# SHT_4_MCU_07349-R5_L10.net
KiCad netlist of a schematic drawn in Altium Designer
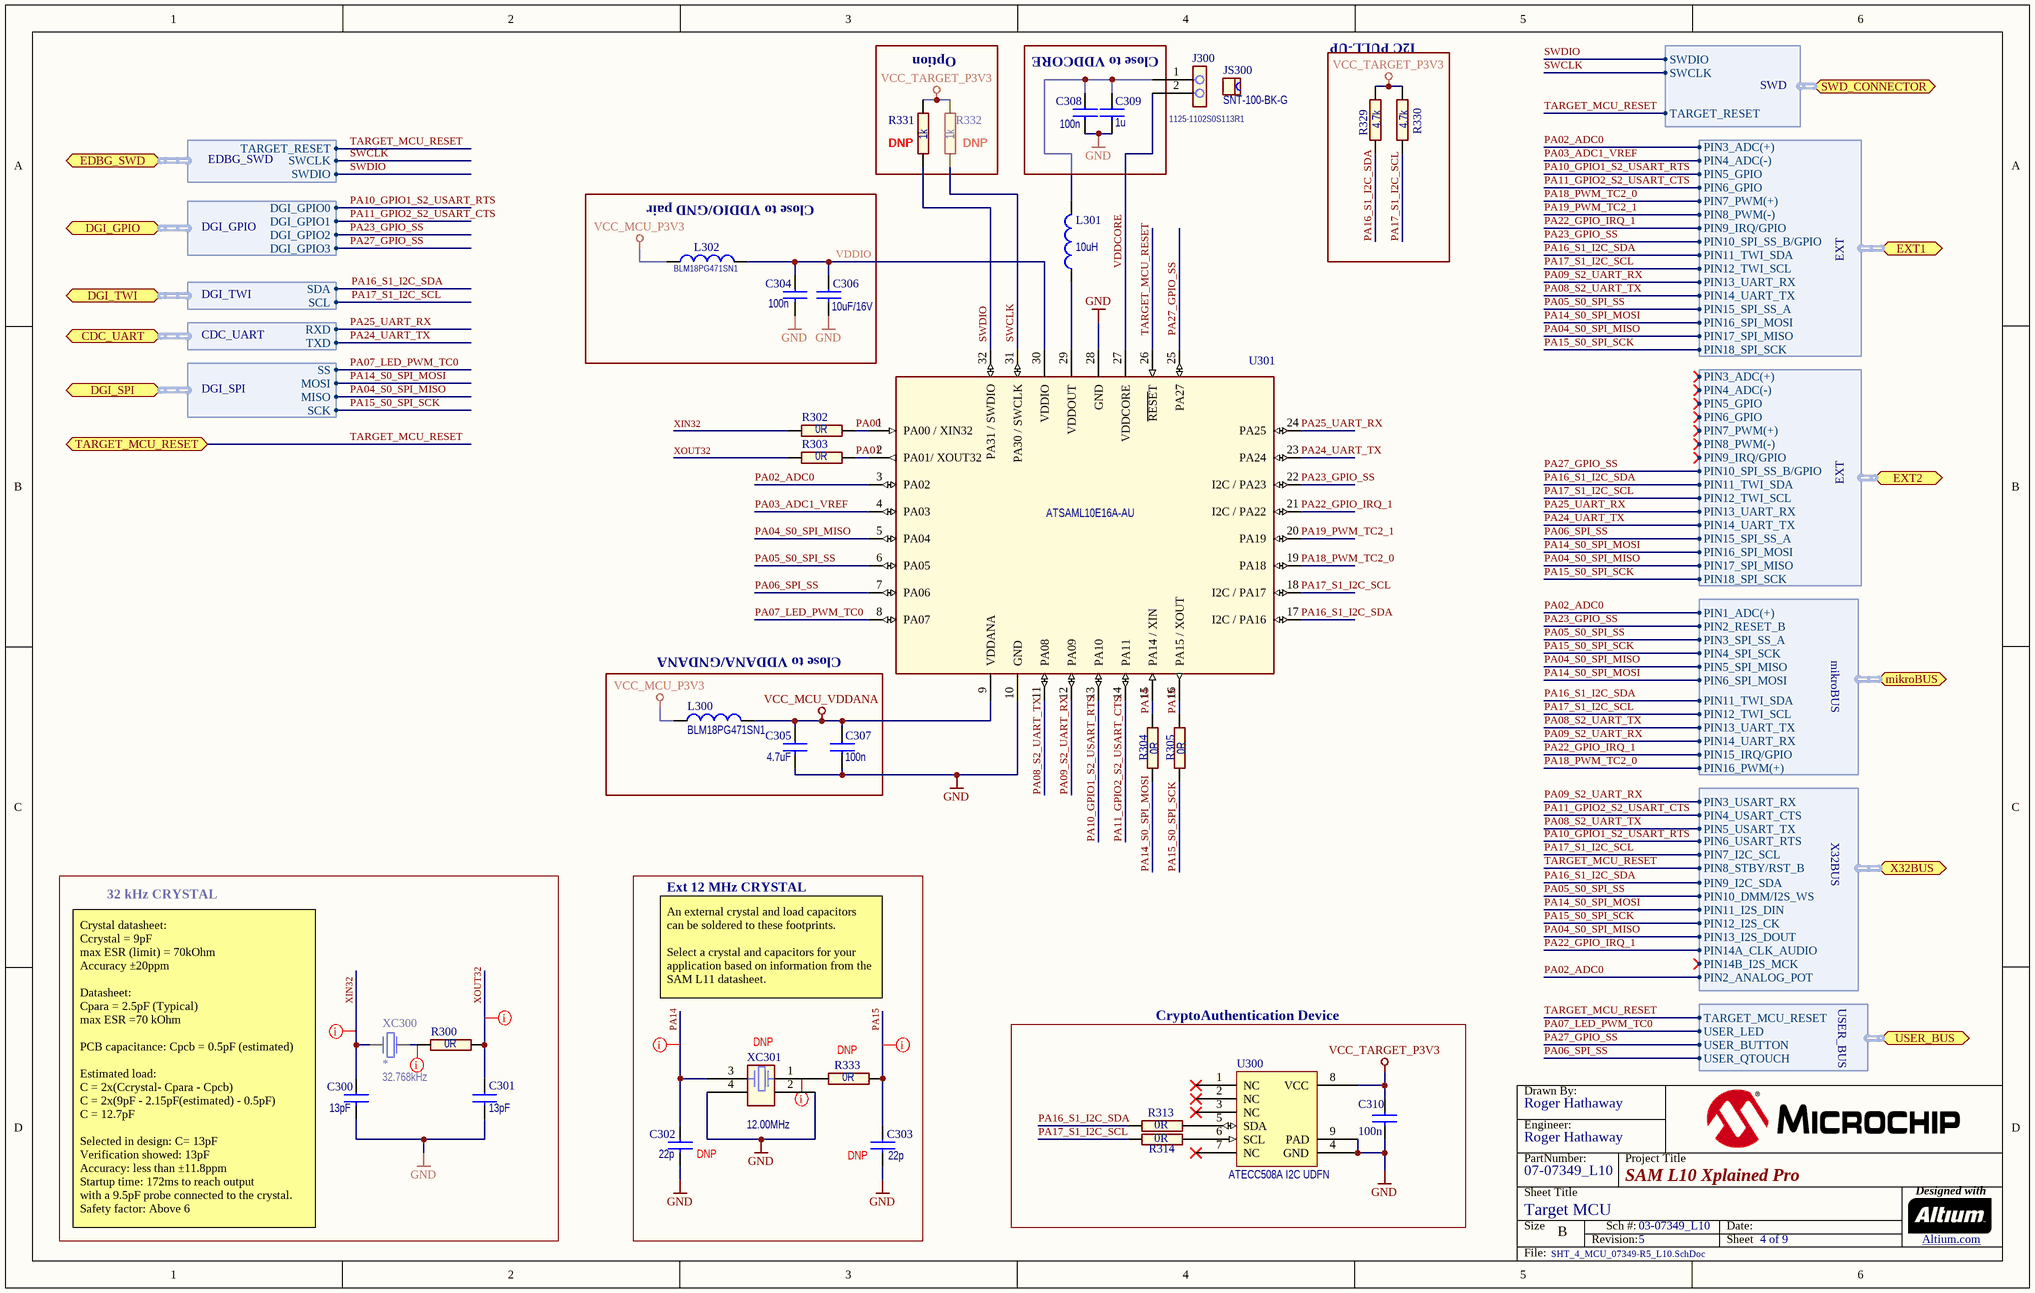
[diagram p0: SHT_4_MCU_07349-R5_L10.SchDoc]

(export (version "E")
  (design (tool "Eeschema 10.0.6"))
  (components
    (comp (ref "C300")
      (value "13pF")
      (footprint "AP1-00053")
      (description "Ceramic capacitor, SMD 0402, NP0, 50V, +/-5%")
      (fields
        (field (name "TOLERANCE") "5%")
        (field (name "MANUFACTURER") "Murata")
        (field (name "VERIFIED BY") "Lars Helge Mo")
      )
      (libsource (lib "AltiumDbLib") (part "CAP-NONPOL"))
    )
    (comp (ref "C301")
      (value "13pF")
      (footprint "AP1-00053")
      (description "Ceramic capacitor, SMD 0402, NP0, 50V, +/-5%")
      (fields
        (field (name "TOLERANCE") "5%")
        (field (name "MANUFACTURER") "Murata")
        (field (name "VERIFIED BY") "Lars Helge Mo")
      )
      (libsource (lib "AltiumDbLib") (part "CAP-NONPOL"))
    )
    (comp (ref "C302")
      (value "22p")
      (footprint "AP1-00001")
      (description "Ceramic capacitor, SMD 0402, NP0, 50V, +/-5%")
      (fields
        (field (name "TOLERANCE") "50V, +/-5%")
        (field (name "MANUFACTURER") "YAGEO CORP")
        (field (name "PLACEMENT") "DNP")
        (field (name "VERIFIED BY") "Lars Helge Mo")
      )
      (libsource (lib "AltiumDbLib") (part "CAP-NONPOL"))
    )
    (comp (ref "C303")
      (value "22p")
      (footprint "AP1-00001")
      (description "Ceramic capacitor, SMD 0402, NP0, 50V, +/-5%")
      (fields
        (field (name "TOLERANCE") "50V, +/-5%")
        (field (name "MANUFACTURER") "YAGEO CORP")
        (field (name "PLACEMENT") "DNP")
        (field (name "VERIFIED BY") "Lars Helge Mo")
      )
      (libsource (lib "AltiumDbLib") (part "CAP-NONPOL"))
    )
    (comp (ref "C304")
      (value "100n")
      (footprint "AP1-00001")
      (description "Ceramic capacitor, SMD 0402, X7R, 16V, +/-10%")
      (fields
        (field (name "TOLERANCE") "16V, +/-10%")
        (field (name "MANUFACTURER") "Kemet")
        (field (name "VERIFIED BY") "Lars Helge Mo")
      )
      (libsource (lib "AltiumDbLib") (part "CAP-NONPOL"))
    )
    (comp (ref "C305")
      (value "4.7uF")
      (footprint "AP1-00039")
      (description "Ceramic capacitor, SMD 0603, X5R, 10V, 10% (de31036)")
      (fields
        (field (name "TOLERANCE") "10%")
        (field (name "MANUFACTURER") "WALSIN Technology Corporation")
        (field (name "VERIFIED BY") "Lars Helge Mo")
      )
      (libsource (lib "AltiumDbLib") (part "CAP-NONPOL"))
    )
    (comp (ref "C306")
      (value "10uF/16V")
      (footprint "AP1-00039")
      (description "Ceramic capacitor, SMD 0603, X5R, 16V, 10UF ± 20% (High Density)")
      (fields
        (field (name "TOLERANCE") "­± 20%")
        (field (name "MANUFACTURER") "Taiyo Yuden")
        (field (name "VERIFIED BY") "Lars Helge Mo")
      )
      (libsource (lib "AltiumDbLib") (part "CAP-NONPOL"))
    )
    (comp (ref "C307")
      (value "100n")
      (footprint "AP1-00001")
      (description "Ceramic capacitor, SMD 0402, X7R, 16V, +/-10%")
      (fields
        (field (name "TOLERANCE") "16V, +/-10%")
        (field (name "MANUFACTURER") "Kemet")
        (field (name "VERIFIED BY") "Lars Helge Mo")
      )
      (libsource (lib "AltiumDbLib") (part "CAP-NONPOL"))
    )
    (comp (ref "C308")
      (value "100n")
      (footprint "AP1-00001")
      (description "Ceramic capacitor, SMD 0402, X7R, 16V, +/-10%")
      (fields
        (field (name "TOLERANCE") "16V, +/-10%")
        (field (name "MANUFACTURER") "Kemet")
        (field (name "VERIFIED BY") "Lars Helge Mo")
      )
      (libsource (lib "AltiumDbLib") (part "CAP-NONPOL"))
    )
    (comp (ref "C309")
      (value "1u")
      (footprint "AP1-00001")
      (description "Ceramic capacitor, SMD 0402, X5R, 6.3V, +/-10% (de26942)")
      (fields
        (field (name "TOLERANCE") "+/-10%")
        (field (name "MANUFACTURER") "Kemet")
        (field (name "VERIFIED BY") "Lars Helge Mo")
      )
      (libsource (lib "AltiumDbLib") (part "CAP-NONPOL"))
    )
    (comp (ref "C310")
      (value "100n")
      (footprint "AltiumDbLib:AP1-00053")
      (description "Ceramic capacitor, SMD 0402, X7R, 16V, +/-10%")
      (fields
        (field (name "TOLERANCE") "16V, +/-10%")
        (field (name "MANUFACTURER") "Kemet")
        (field (name "VERIFIED BY") "Lars Helge Mo")
      )
      (libsource (lib "AltiumDbLib") (part "CAP-NONPOL"))
    )
    (comp (ref "J300")
      (value "HEADER 1x2")
      (footprint "AP8-01074")
      (description "1x2 pin header, 2.54mm pitch, Pin-in-Paste THM")
      (fields
        (field (name "MANUFACTURER") "WCON HARDWARE ELECTRONICS CO., LTD")
        (field (name "MPN") "1125-1102S0S113R1")
        (field (name "VERIFIED BY") "Lars Helge")
      )
      (libsource (lib "AltiumDbLib") (part "HEADER 1x2"))
    )
    (comp (ref "JS300")
      (value "SNT-100-BK-G")
      (footprint "AP8-00525")
      (description "Jumper cap for 2.54mm pinheader")
      (fields
        (field (name "MANUFACTURER") "SAMTEC")
        (field (name "Comment") "To be used by request from ESCATEC")
        (field (name "VERIFIED BY") "Lars Helge Mo")
      )
      (libsource (lib "AltiumDbLib") (part "JUMPER_CAP"))
    )
    (comp (ref "L300")
      (value "BLM18PG471SN1")
      (footprint "AP3-00005")
      (description "SMD RF inductor 0603. Z=470Ohm (@100MHz), Max R(dc)=0.20Ohm, Max current=1A")
      (fields
        (field (name "MANUFACTURER") "Murata")
        (field (name "Comment") "INDUCTOR")
        (field (name "VERIFIED BY") "Lars Helge Mo")
      )
      (libsource (lib "") (part "INDUCTOR_1"))
    )
    (comp (ref "L301")
      (value "10uH")
      (footprint "AP3-00157")
      (description "SMD power inductor, LxWxH=3.0x3.0x2.0mm, Isat=2.35A, Ir=1.2A, Rdc=0.28Ohm, 20%")
      (fields
        (field (name "TOLERANCE") "20%")
        (field (name "MANUFACTURER") "Wurth Elektronik")
        (field (name "VERIFIED BY") "Lars Helge Mo")
      )
      (libsource (lib "AltiumDbLib") (part "INDUCTOR"))
    )
    (comp (ref "L302")
      (value "BLM18PG471SN1")
      (footprint "AP3-00005")
      (description "SMD RF inductor 0603. Z=470Ohm (@100MHz), Max R(dc)=0.20Ohm, Max current=1A")
      (fields
        (field (name "MANUFACTURER") "Murata")
        (field (name "Comment") "INDUCTOR")
        (field (name "VERIFIED BY") "Lars Helge Mo")
      )
      (libsource (lib "AltiumDbLib") (part "INDUCTOR"))
    )
    (comp (ref "R300")
      (value "0R")
      (footprint "AP2-00000")
      (description "RES 0.0 OHM 1/16W 0402 SMD")
      (fields
        (field (name "TOLERANCE") "1 %")
        (field (name "MANUFACTURER") "(n/a)")
        (field (name "VERIFIED BY") "Lars Helge Mo")
      )
      (libsource (lib "") (part "R2_2"))
    )
    (comp (ref "R302")
      (value "0R")
      (footprint "AP2-00000")
      (description "RES 0.0 OHM 1/16W 0402 SMD")
      (fields
        (field (name "TOLERANCE") "1 %")
        (field (name "MANUFACTURER") "(n/a)")
        (field (name "VERIFIED BY") "Lars Helge Mo")
      )
      (libsource (lib "") (part "R2_2"))
    )
    (comp (ref "R303")
      (value "0R")
      (footprint "AP2-00000")
      (description "RES 0.0 OHM 1/16W 0402 SMD")
      (fields
        (field (name "TOLERANCE") "1 %")
        (field (name "MANUFACTURER") "(n/a)")
        (field (name "VERIFIED BY") "Lars Helge Mo")
      )
      (libsource (lib "") (part "R2_2"))
    )
    (comp (ref "R304")
      (value "0R")
      (footprint "AP2-00000")
      (description "RES 0.0 OHM 1/16W 0402 SMD")
      (fields
        (field (name "TOLERANCE") "1 %")
        (field (name "MANUFACTURER") "(n/a)")
        (field (name "VERIFIED BY") "Lars Helge Mo")
      )
      (libsource (lib "") (part "R2_1"))
    )
    (comp (ref "R305")
      (value "0R")
      (footprint "AP2-00000")
      (description "RES 0.0 OHM 1/16W 0402 SMD")
      (fields
        (field (name "TOLERANCE") "1 %")
        (field (name "MANUFACTURER") "(n/a)")
        (field (name "VERIFIED BY") "Lars Helge Mo")
      )
      (libsource (lib "") (part "R2_1"))
    )
    (comp (ref "R313")
      (value "0R")
      (footprint "AP2-00000")
      (description "RES 0.0 OHM 1/16W 0402 SMD")
      (fields
        (field (name "TOLERANCE") "1 %")
        (field (name "MANUFACTURER") "(n/a)")
        (field (name "VERIFIED BY") "Lars Helge Mo")
      )
      (libsource (lib "") (part "R2_3"))
    )
    (comp (ref "R314")
      (value "0R")
      (footprint "AP2-00000")
      (description "RES 0.0 OHM 1/16W 0402 SMD")
      (fields
        (field (name "TOLERANCE") "1 %")
        (field (name "MANUFACTURER") "(n/a)")
        (field (name "VERIFIED BY") "Lars Helge Mo")
      )
      (libsource (lib "") (part "R2_3"))
    )
    (comp (ref "R329")
      (value "4.7k")
      (footprint "AP2-00032")
      (description "Thick film resistor, SMD 0402, 1/16W, 5%")
      (fields
        (field (name "TOLERANCE") "5%")
        (field (name "MANUFACTURER") "(n/a)")
        (field (name "VERIFIED BY") "Lars Helge Mo")
      )
      (libsource (lib "AltiumDbLib") (part "R2"))
    )
    (comp (ref "R330")
      (value "4.7k")
      (footprint "AP2-00032")
      (description "Thick film resistor, SMD 0402, 1/16W, 5%")
      (fields
        (field (name "TOLERANCE") "5%")
        (field (name "MANUFACTURER") "(n/a)")
        (field (name "VERIFIED BY") "Lars Helge Mo")
      )
      (libsource (lib "AltiumDbLib") (part "R2"))
    )
    (comp (ref "R331")
      (value "1k")
      (footprint "AP2-00000")
      (description "Thick film resistor, SMD 0402, 1/16W, 1%")
      (fields
        (field (name "TOLERANCE") "1 %")
        (field (name "MANUFACTURER") "ASJ")
        (field (name "PLACEMENT") "DNP")
        (field (name "VERIFIED BY") "Lars Helge Mo")
      )
      (libsource (lib "AltiumDbLib") (part "R2"))
    )
    (comp (ref "R332")
      (value "1k")
      (footprint "AP2-00000")
      (description "Thick film resistor, SMD 0402, 1/16W, 1%")
      (fields
        (field (name "TOLERANCE") "1 %")
        (field (name "MANUFACTURER") "ASJ")
        (field (name "PLACEMENT") "DNP")
        (field (name "VERIFIED BY") "Lars Helge Mo")
      )
      (libsource (lib "AltiumDbLib") (part "R2"))
    )
    (comp (ref "R333")
      (value "0R")
      (footprint "AP2-00000")
      (description "RES 0.0 OHM 1/16W 0402 SMD")
      (fields
        (field (name "TOLERANCE") "1 %")
        (field (name "MANUFACTURER") "(n/a)")
        (field (name "PLACEMENT") "DNP")
        (field (name "VERIFIED BY") "Lars Helge Mo")
      )
      (libsource (lib "AltiumDbLib") (part "R2"))
    )
    (comp (ref "U300")
      (value "ATECC508A I2C UDFN")
      (footprint "AP6-00409")
      (description "ATECC508A with an I2C Interface and a 8 Pin UDFN Package with Paddle")
      (fields (field (name "MANUFACTURER") "MICROCHIP") (field (name "MPN") "ATECC508A-MAHDA-T"))
      (libsource (lib "AltiumDbLib") (part "ATECC508A_I2C_UDFN"))
    )
    (comp (ref "U301")
      (value "ATSAML10E16A-AU")
      (footprint "AP6-00508")
      (description "32 Bit Ultra Low Power MCU w/ 64K Flash")
      (fields (field (name "MANUFACTURER") "Microchip") (field (name "VERIFIED BY") "*"))
      (libsource (lib "AltiumDbLib") (part "ATSAML10E16A-AU"))
    )
    (comp (ref "XC300")
      (value "*")
      (footprint "AP7-00090")
      (description "Kyocera ST3215SB32768E0HPWBB, 32.768kHz, 9pF, SMD tuning fork crystal")
      (fields
        (field (name "ALTIUM_VALUE") "32.768kHz")
        (field (name "TOLERANCE") "Â±20ppm")
        (field (name "MANUFACTURER") "Kyocera Crystal Device Corporation")
        (field (name "VERIFIED BY") "Sveinung Helgeland")
      )
      (libsource (lib "AltiumDbLib") (part "CRYSTAL"))
    )
    (comp (ref "XC301")
      (value "12.00MHz")
      (footprint "AP7-00039")
      (description "Fox FQ5032B 12.0000MHz  20pF SMD crystal 738B-12")
      (fields
        (field (name "TOLERANCE") "Â±30ppm")
        (field (name "MANUFACTURER") "Fox  Electronics")
        (field (name "PLACEMENT") "DNP")
        (field (name "VERIFIED BY") "Ketil Skjerve")
      )
      (libsource (lib "AltiumDbLib") (part "CRYSTAL1324"))
    )
  )
  (nets
    (net (code "11") (name "/PA00") (class "Default")
      (node (ref "R302") (pin "2") (pinfunction "2_2") (pintype "passive"))
      (node (ref "U301") (pin "1") (pinfunction "PA00_/_XIN32_1") (pintype "input"))
    )
    (net (code "12") (name "/PA01") (class "Default")
      (node (ref "R303") (pin "2") (pinfunction "2_2") (pintype "passive"))
      (node (ref "U301") (pin "2") (pinfunction "PA01/_XOUT32_2") (pintype "output"))
    )
    (net (code "13") (name "/PA02_ADC0") (class "Default")
      (node (ref "U301") (pin "3") (pinfunction "PA02_3") (pintype "bidirectional"))
    )
    (net (code "14") (name "/PA03_ADC1_VREF") (class "Default")
      (node (ref "U301") (pin "4") (pinfunction "PA03_4") (pintype "bidirectional"))
    )
    (net (code "15") (name "/PA04_S0_SPI_MISO") (class "Default")
      (node (ref "U301") (pin "5") (pinfunction "PA04_5") (pintype "bidirectional"))
    )
    (net (code "16") (name "/PA05_S0_SPI_SS") (class "Default")
      (node (ref "U301") (pin "6") (pinfunction "PA05_6") (pintype "bidirectional"))
    )
    (net (code "17") (name "/PA06_SPI_SS") (class "Default")
      (node (ref "U301") (pin "7") (pinfunction "PA06_7") (pintype "bidirectional"))
    )
    (net (code "18") (name "/PA07_LED_PWM_TC0") (class "Default")
      (node (ref "U301") (pin "8") (pinfunction "PA07_8") (pintype "bidirectional"))
    )
    (net (code "19") (name "/PA08_S2_UART_TX") (class "Default")
      (node (ref "U301") (pin "11") (pinfunction "PA08_11") (pintype "bidirectional"))
    )
    (net (code "20") (name "/PA09_S2_UART_RX") (class "Default")
      (node (ref "U301") (pin "12") (pinfunction "PA09_12") (pintype "bidirectional"))
    )
    (net (code "21") (name "/PA10_GPIO1_S2_USART_RTS") (class "Default")
      (node (ref "U301") (pin "13") (pinfunction "PA10_13") (pintype "bidirectional"))
    )
    (net (code "22") (name "/PA11_GPIO2_S2_USART_CTS") (class "Default")
      (node (ref "U301") (pin "14") (pinfunction "PA11_14") (pintype "bidirectional"))
    )
    (net (code "23") (name "/PA14") (class "Default")
      (node (ref "C302") (pin "1") (pinfunction "1_1") (pintype "passive"))
      (node (ref "R304") (pin "2") (pinfunction "2_2") (pintype "passive"))
      (node (ref "U301") (pin "15") (pinfunction "PA14_/_XIN_15") (pintype "input"))
      (node (ref "XC301") (pin "3") (pinfunction "3_3") (pintype "passive"))
    )
    (net (code "24") (name "/PA14_S0_SPI_MOSI") (class "Default")
      (node (ref "R304") (pin "1") (pinfunction "1_1") (pintype "passive"))
    )
    (net (code "25") (name "/PA15") (class "Default")
      (node (ref "C303") (pin "1") (pinfunction "1_1") (pintype "passive"))
      (node (ref "R305") (pin "2") (pinfunction "2_2") (pintype "passive"))
      (node (ref "R333") (pin "1") (pinfunction "1_1") (pintype "passive"))
      (node (ref "U301") (pin "16") (pinfunction "PA15_/_XOUT_16") (pintype "output"))
    )
    (net (code "26") (name "/PA15_S0_SPI_SCK") (class "Default")
      (node (ref "R305") (pin "1") (pinfunction "1_1") (pintype "passive"))
    )
    (net (code "27") (name "/PA16_S1_I2C_SDA") (class "Default")
      (node (ref "R313") (pin "2") (pinfunction "2_2") (pintype "passive"))
      (node (ref "R329") (pin "2") (pinfunction "2_2") (pintype "passive"))
      (node (ref "U301") (pin "17") (pinfunction "I2C_/_PA16_17") (pintype "bidirectional"))
    )
    (net (code "28") (name "/PA17_S1_I2C_SCL") (class "Default")
      (node (ref "R314") (pin "2") (pinfunction "2_2") (pintype "passive"))
      (node (ref "R330") (pin "2") (pinfunction "2_2") (pintype "passive"))
      (node (ref "U301") (pin "18") (pinfunction "I2C_/_PA17_18") (pintype "bidirectional"))
    )
    (net (code "29") (name "/PA18_PWM_TC2_0") (class "Default")
      (node (ref "U301") (pin "19") (pinfunction "PA18_19") (pintype "bidirectional"))
    )
    (net (code "30") (name "/PA19_PWM_TC2_1") (class "Default")
      (node (ref "U301") (pin "20") (pinfunction "PA19_20") (pintype "bidirectional"))
    )
    (net (code "31") (name "/PA22_GPIO_IRQ_1") (class "Default")
      (node (ref "U301") (pin "21") (pinfunction "I2C_/_PA22_21") (pintype "bidirectional"))
    )
    (net (code "32") (name "/PA23_GPIO_SS") (class "Default")
      (node (ref "U301") (pin "22") (pinfunction "I2C_/_PA23_22") (pintype "bidirectional"))
    )
    (net (code "33") (name "/PA24_UART_TX") (class "Default")
      (node (ref "U301") (pin "23") (pinfunction "PA24_23") (pintype "bidirectional"))
    )
    (net (code "34") (name "/PA25_UART_RX") (class "Default")
      (node (ref "U301") (pin "24") (pinfunction "PA25_24") (pintype "bidirectional"))
    )
    (net (code "35") (name "/PA27_GPIO_SS") (class "Default")
      (node (ref "U301") (pin "25") (pinfunction "PA27_25") (pintype "bidirectional"))
    )
    (net (code "36") (name "/SWCLK") (class "Default")
      (node (ref "R332") (pin "2") (pinfunction "2_2") (pintype "passive"))
      (node (ref "U301") (pin "31") (pinfunction "PA30_/_SWCLK_31") (pintype "bidirectional"))
    )
    (net (code "37") (name "/SWDIO") (class "Default")
      (node (ref "R331") (pin "2") (pinfunction "2_2") (pintype "passive"))
      (node (ref "U301") (pin "32") (pinfunction "PA31_/_SWDIO_32") (pintype "bidirectional"))
    )
    (net (code "38") (name "/TARGET_MCU_RESET") (class "Default")
      (node (ref "U301") (pin "26") (pinfunction "~{RESE}T_26") (pintype "input"))
    )
    (net (code "39") (name "/VDDCORE") (class "Default")
      (node (ref "J300") (pin "2") (pinfunction "2_2") (pintype "passive"))
      (node (ref "U301") (pin "27") (pinfunction "VDDCORE_27") (pintype "power_in"))
    )
    (net (code "40") (name "/VDDIO") (class "Default")
      (node (ref "C304") (pin "1") (pinfunction "1_1") (pintype "passive"))
      (node (ref "C306") (pin "1") (pinfunction "1_1") (pintype "passive"))
      (node (ref "L302") (pin "1") (pinfunction "1_1") (pintype "passive"))
      (node (ref "U301") (pin "30") (pinfunction "VDDIO_30") (pintype "power_in"))
    )
    (net (code "41") (name "/XIN32") (class "Default")
      (node (ref "C300") (pin "1") (pinfunction "1_1") (pintype "passive"))
      (node (ref "R302") (pin "1") (pinfunction "1_1") (pintype "passive"))
      (node (ref "XC300") (pin "2") (pinfunction "2_2") (pintype "passive"))
    )
    (net (code "42") (name "/XOUT32") (class "Default")
      (node (ref "C301") (pin "1") (pinfunction "1_1") (pintype "passive"))
      (node (ref "R300") (pin "2") (pinfunction "2_2") (pintype "passive"))
      (node (ref "R303") (pin "1") (pinfunction "1_1") (pintype "passive"))
    )
    (net (code "53") (name "GND") (class "Default")
      (node (ref "C300") (pin "2") (pinfunction "2_2") (pintype "passive"))
      (node (ref "C301") (pin "2") (pinfunction "2_2") (pintype "passive"))
      (node (ref "C302") (pin "2") (pinfunction "2_2") (pintype "passive"))
      (node (ref "C303") (pin "2") (pinfunction "2_2") (pintype "passive"))
      (node (ref "C304") (pin "2") (pinfunction "2_2") (pintype "passive"))
      (node (ref "C305") (pin "2") (pinfunction "2_2") (pintype "passive"))
      (node (ref "C306") (pin "2") (pinfunction "2_2") (pintype "passive"))
      (node (ref "C307") (pin "2") (pinfunction "2_2") (pintype "passive"))
      (node (ref "C308") (pin "2") (pinfunction "2_2") (pintype "passive"))
      (node (ref "C309") (pin "2") (pinfunction "2_2") (pintype "passive"))
      (node (ref "C310") (pin "2") (pinfunction "2_2") (pintype "passive"))
      (node (ref "U300") (pin "4") (pinfunction "GND_4") (pintype "power_in"))
      (node (ref "U300") (pin "9") (pinfunction "PAD_9") (pintype "power_in"))
      (node (ref "U301") (pin "10") (pinfunction "GND_10") (pintype "passive"))
      (node (ref "U301") (pin "28") (pinfunction "GND_28") (pintype "passive"))
      (node (ref "XC301") (pin "2") (pinfunction "2_2") (pintype "passive"))
      (node (ref "XC301") (pin "4") (pinfunction "4_4") (pintype "passive"))
    )
    (net (code "54") (name "Net-(C308-Pad1)") (class "Default")
      (node (ref "C308") (pin "1") (pinfunction "1_1") (pintype "passive"))
      (node (ref "C309") (pin "1") (pinfunction "1_1") (pintype "passive"))
      (node (ref "J300") (pin "1") (pinfunction "1_1") (pintype "passive"))
      (node (ref "L301") (pin "1") (pinfunction "1_1") (pintype "passive"))
    )
    (net (code "55") (name "Net-(R300-Pad1)") (class "Default")
      (node (ref "R300") (pin "1") (pinfunction "1_1") (pintype "passive"))
      (node (ref "XC300") (pin "1") (pinfunction "1_1") (pintype "passive"))
    )
    (net (code "56") (name "Net-(R333-Pad2)") (class "Default")
      (node (ref "R333") (pin "2") (pinfunction "2_2") (pintype "passive"))
      (node (ref "XC301") (pin "1") (pinfunction "1_1") (pintype "passive"))
    )
    (net (code "57") (name "Net-(U300-SCL)") (class "Default")
      (node (ref "R314") (pin "1") (pinfunction "1_1") (pintype "passive"))
      (node (ref "U300") (pin "6") (pinfunction "SCL_6") (pintype "input"))
    )
    (net (code "58") (name "Net-(U300-SDA)") (class "Default")
      (node (ref "R313") (pin "1") (pinfunction "1_1") (pintype "passive"))
      (node (ref "U300") (pin "5") (pinfunction "SDA_5") (pintype "bidirectional"))
    )
    (net (code "59") (name "Net-(U301-VDDOUT)") (class "Default")
      (node (ref "L301") (pin "2") (pinfunction "2_2") (pintype "passive"))
      (node (ref "U301") (pin "29") (pinfunction "VDDOUT_29") (pintype "power_in"))
    )
    (net (code "60") (name "VCC_MCU_P3V3") (class "Default")
      (node (ref "L300") (pin "1") (pinfunction "1_1") (pintype "passive"))
      (node (ref "L302") (pin "2") (pinfunction "2_2") (pintype "passive"))
    )
    (net (code "61") (name "VCC_MCU_VDDANA") (class "Default")
      (node (ref "C305") (pin "1") (pinfunction "1_1") (pintype "passive"))
      (node (ref "C307") (pin "1") (pinfunction "1_1") (pintype "passive"))
      (node (ref "L300") (pin "2") (pinfunction "2_2") (pintype "passive"))
      (node (ref "U301") (pin "9") (pinfunction "VDDANA_9") (pintype "power_in"))
    )
    (net (code "62") (name "VCC_TARGET_P3V3") (class "Default")
      (node (ref "C310") (pin "1") (pinfunction "1_1") (pintype "passive"))
      (node (ref "R329") (pin "1") (pinfunction "1_1") (pintype "passive"))
      (node (ref "R330") (pin "1") (pinfunction "1_1") (pintype "passive"))
      (node (ref "R331") (pin "1") (pinfunction "1_1") (pintype "passive"))
      (node (ref "R332") (pin "1") (pinfunction "1_1") (pintype "passive"))
      (node (ref "U300") (pin "8") (pinfunction "VCC_8") (pintype "power_in"))
    )
    (net (code "63") (name "unconnected-(U300-NC-Pad1)") (class "Default")
      (node (ref "U300") (pin "1") (pinfunction "NC_1") (pintype "passive+no_connect"))
    )
    (net (code "64") (name "unconnected-(U300-NC-Pad2)") (class "Default")
      (node (ref "U300") (pin "2") (pinfunction "NC_2") (pintype "passive+no_connect"))
    )
    (net (code "65") (name "unconnected-(U300-NC-Pad3)") (class "Default")
      (node (ref "U300") (pin "3") (pinfunction "NC_3") (pintype "passive+no_connect"))
    )
    (net (code "66") (name "unconnected-(U300-NC-Pad7)") (class "Default")
      (node (ref "U300") (pin "7") (pinfunction "NC_7") (pintype "passive+no_connect"))
    )
  )
)
